# ivo_B_v1_1.net
KiCad netlist of a schematic drawn in EAGLE
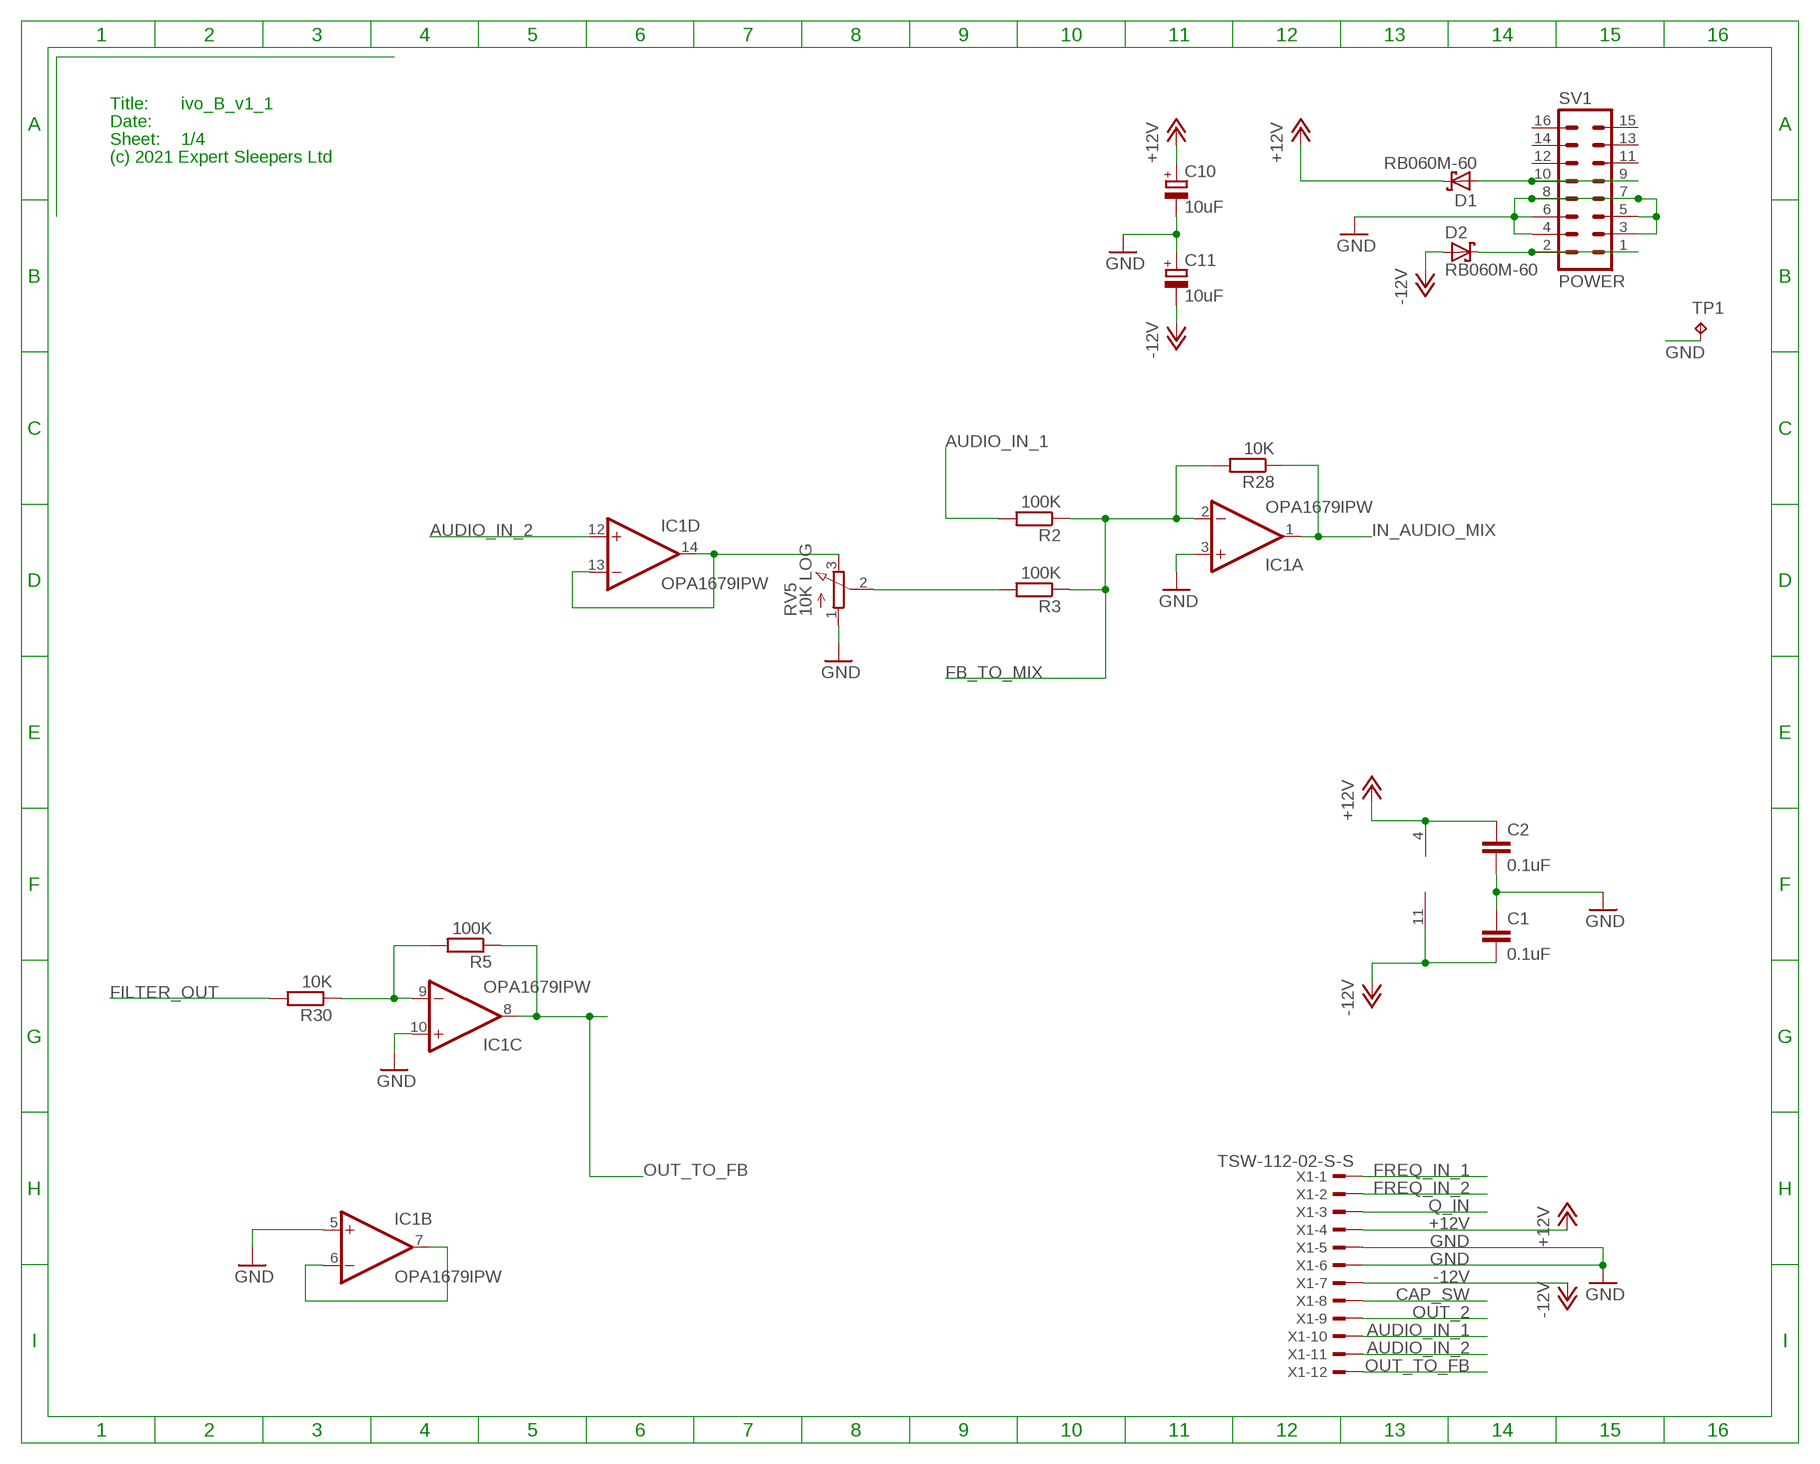
[diagram p0: schematic, sheet 1]
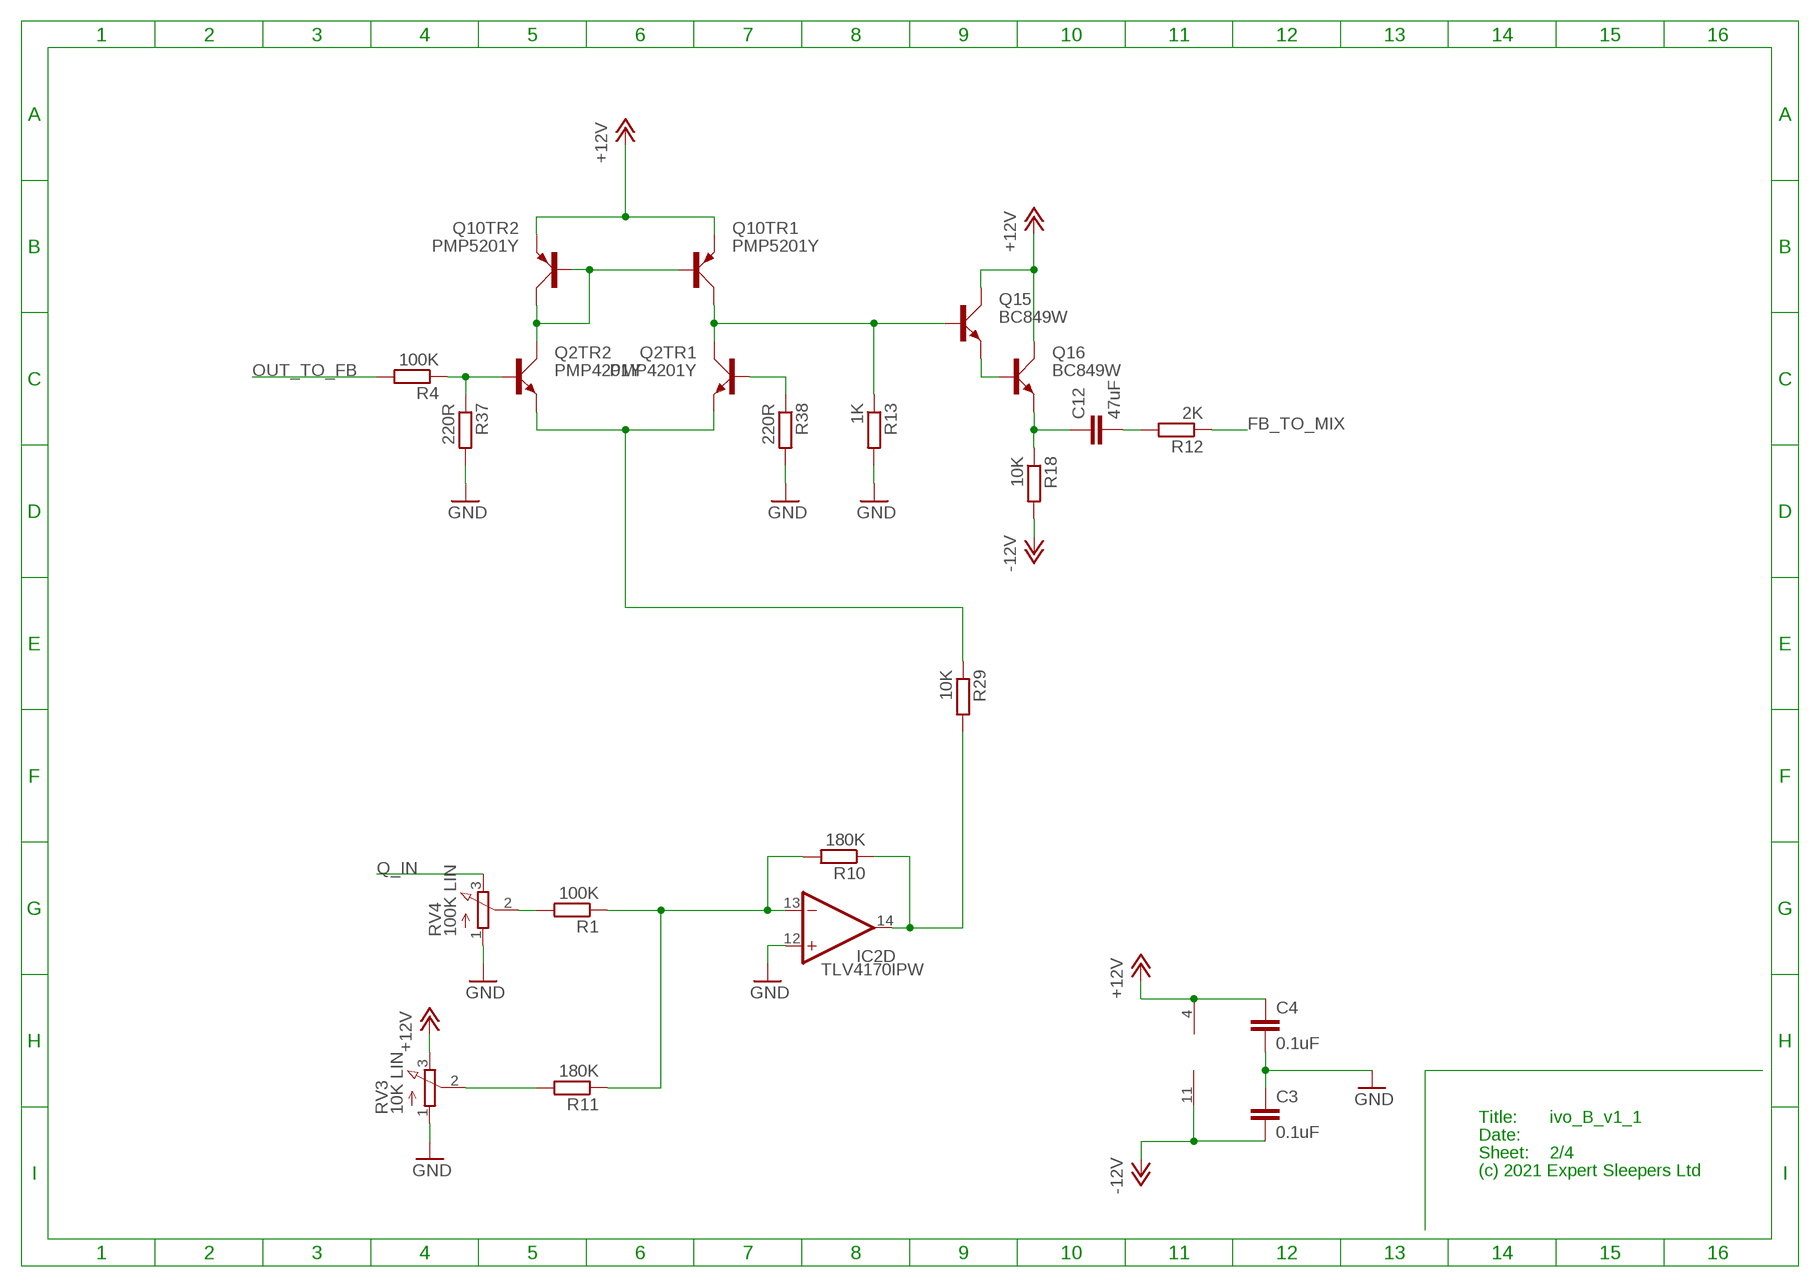
[diagram p1: schematic, sheet 2]
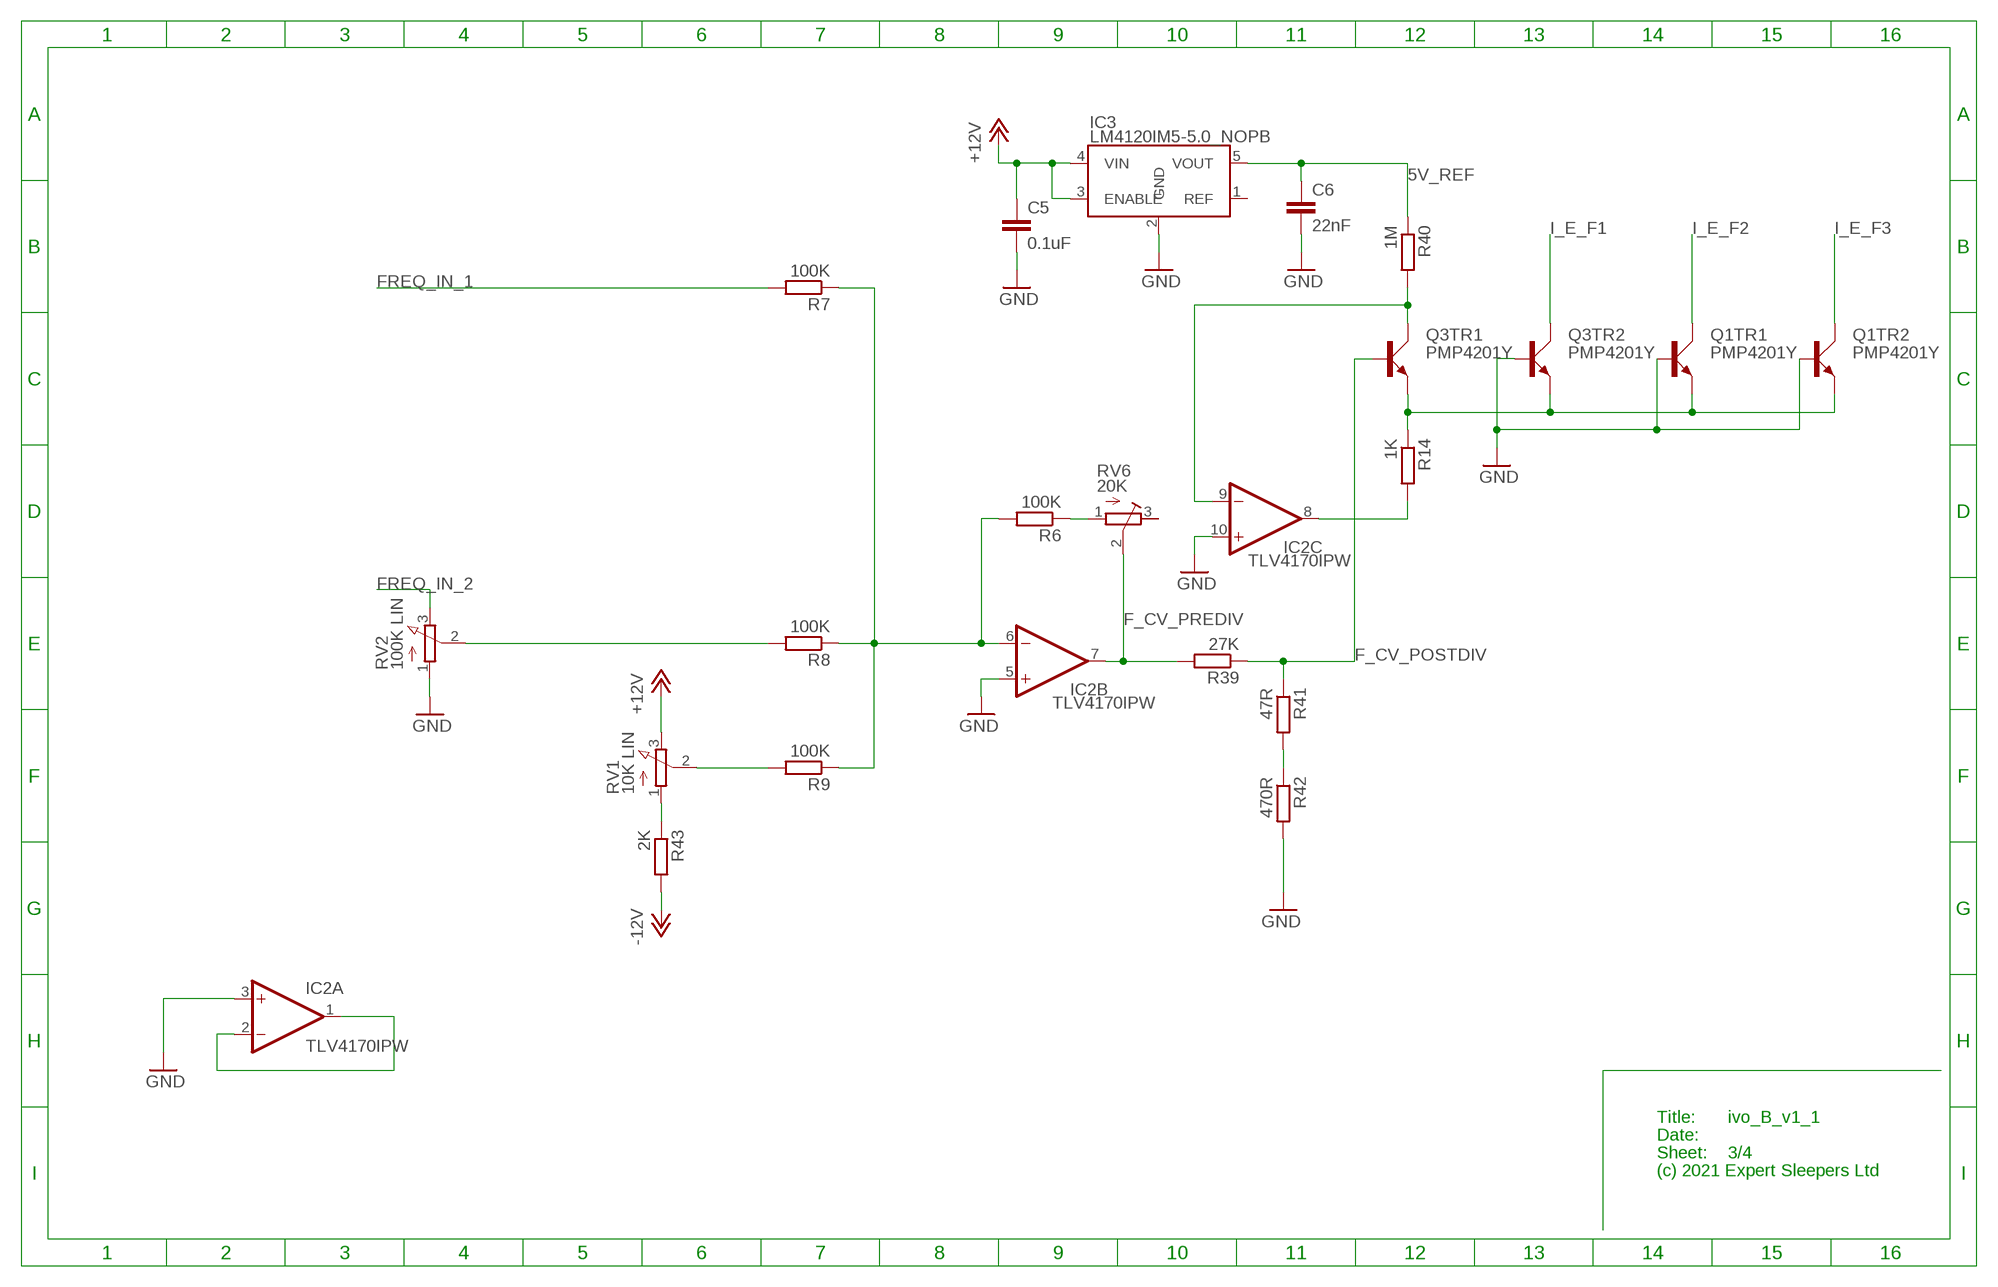
[diagram p2: schematic, sheet 3]
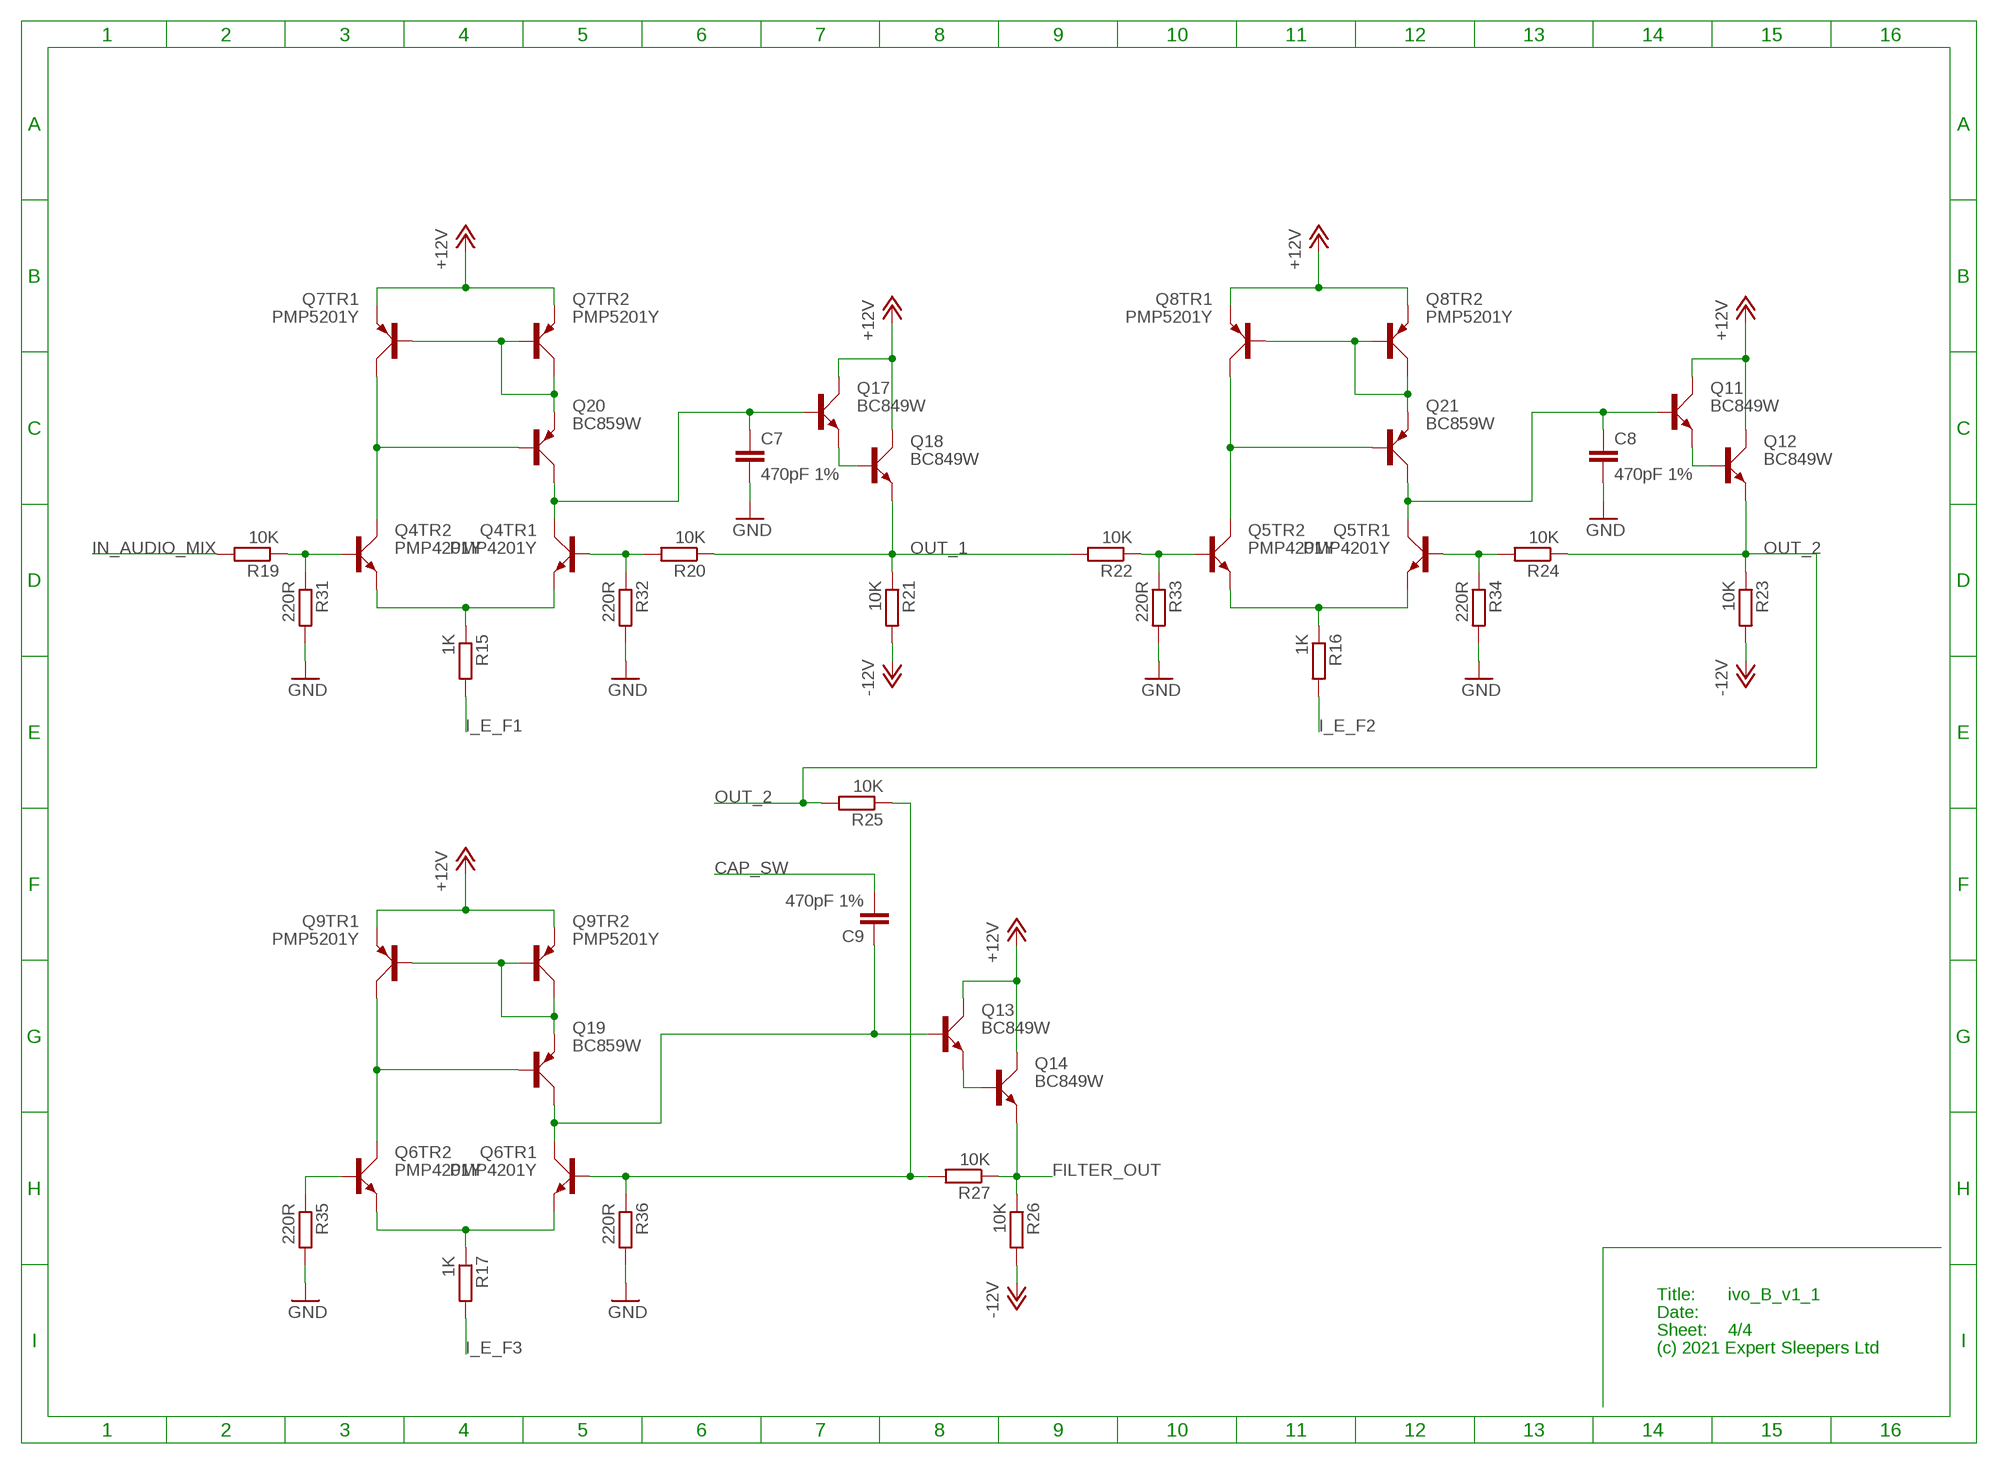
[diagram p3: schematic, sheet 4]

(export (version "E")
  (design (tool "Eeschema 10.0.6"))
  (components
    (comp (ref "C5")
      (value "0.1uF")
      (footprint "eagle-import:C0402")
      (libsource (lib "eagle-import") (part "C-EUC0402"))
    )
    (comp (ref "C6")
      (value "22nF")
      (footprint "eagle-import:C0402")
      (libsource (lib "eagle-import") (part "C-EUC0402"))
    )
    (comp (ref "IC2")
      (value "TLV4170IPW")
      (footprint "eagle-import:PW_R-PDSO-G14")
      (libsource (lib "eagle-import") (part "TL074PW"))
    )
    (comp (ref "IC3")
      (value "LM4120IM5-5.0_NOPB")
      (footprint "eagle-import:SOT95P280X145-5N")
      (fields
        (field (name "ARROW_PART_NUMBER") "LM4120IM5-5.0/NOPB")
        (field (name "MOUSER_PART_NUMBER") "926-LM4120IM550NOPB")
      )
      (libsource (lib "eagle-import") (part "LM4120IM5-5.0_NOPB"))
    )
    (comp (ref "Q1")
      (value "PMP4201Y")
      (footprint "eagle-import:SOT65P210X110-6N")
      (fields
        (field (name "ARROW_PART_NUMBER") "PMP4201Y,135")
        (field (name "MOUSER_PART_NUMBER") "771-PMP4201Y135")
      )
      (libsource (lib "eagle-import") (part "PMP4201Y"))
    )
    (comp (ref "Q3")
      (value "PMP4201Y")
      (footprint "eagle-import:SOT65P210X110-6N")
      (fields
        (field (name "ARROW_PART_NUMBER") "PMP4201Y,135")
        (field (name "MOUSER_PART_NUMBER") "771-PMP4201Y135")
      )
      (libsource (lib "eagle-import") (part "PMP4201Y"))
    )
    (comp (ref "R6")
      (value "100K")
      (footprint "eagle-import:R0603")
      (libsource (lib "eagle-import") (part "R-EU_R0603"))
    )
    (comp (ref "R7")
      (value "100K")
      (footprint "eagle-import:R0603")
      (libsource (lib "eagle-import") (part "R-EU_R0603"))
    )
    (comp (ref "R8")
      (value "100K")
      (footprint "eagle-import:R0603")
      (libsource (lib "eagle-import") (part "R-EU_R0603"))
    )
    (comp (ref "R9")
      (value "100K")
      (footprint "eagle-import:R0603")
      (libsource (lib "eagle-import") (part "R-EU_R0603"))
    )
    (comp (ref "R14")
      (value "1K")
      (footprint "eagle-import:R0603")
      (libsource (lib "eagle-import") (part "R-EU_R0603"))
    )
    (comp (ref "R39")
      (value "27K")
      (footprint "eagle-import:R0603")
      (libsource (lib "eagle-import") (part "R-EU_R0603"))
    )
    (comp (ref "R40")
      (value "1M")
      (footprint "eagle-import:R0603")
      (libsource (lib "eagle-import") (part "R-EU_R0603"))
    )
    (comp (ref "R41")
      (value "47R")
      (footprint "eagle-import:R0603")
      (libsource (lib "eagle-import") (part "R-EU_R0603"))
    )
    (comp (ref "R42")
      (value "470R")
      (footprint "eagle-import:R1206")
      (libsource (lib "eagle-import") (part "R-EU_R1206"))
    )
    (comp (ref "R43")
      (value "2K")
      (footprint "eagle-import:R0603")
      (libsource (lib "eagle-import") (part "R-EU_R0603"))
    )
    (comp (ref "RV1")
      (value "10K LIN")
      (footprint "eagle-import:RD1610NOA0X")
      (libsource (lib "eagle-import") (part "RD1610NOA0X"))
    )
    (comp (ref "RV2")
      (value "100K LIN")
      (footprint "eagle-import:RD1610NOA0X")
      (libsource (lib "eagle-import") (part "RD1610NOA0X"))
    )
    (comp (ref "RV6")
      (value "20K")
      (footprint "eagle-import:TC33X")
      (libsource (lib "eagle-import") (part "TC33X"))
    )
    (comp (ref "C1")
      (value "0.1uF")
      (footprint "eagle-import:C0402")
      (libsource (lib "eagle-import") (part "C-EUC0402"))
    )
    (comp (ref "C2")
      (value "0.1uF")
      (footprint "eagle-import:C0402")
      (libsource (lib "eagle-import") (part "C-EUC0402"))
    )
    (comp (ref "C10")
      (value "10uF")
      (footprint "eagle-import:UD-4X5,8_NICHICON")
      (libsource (lib "eagle-import") (part "CPOL-EUUD-4X5,8"))
    )
    (comp (ref "C11")
      (value "10uF")
      (footprint "eagle-import:UD-4X5,8_NICHICON")
      (libsource (lib "eagle-import") (part "CPOL-EUUD-4X5,8"))
    )
    (comp (ref "D1")
      (value "RB060M-60")
      (footprint "eagle-import:SOD123FL")
      (libsource (lib "eagle-import") (part "RB060M-60"))
    )
    (comp (ref "D2")
      (value "RB060M-60")
      (footprint "eagle-import:SOD123FL")
      (libsource (lib "eagle-import") (part "RB060M-60"))
    )
    (comp (ref "IC1")
      (value "OPA1679IPW")
      (footprint "eagle-import:PW_R-PDSO-G14")
      (libsource (lib "eagle-import") (part "TL074PW"))
    )
    (comp (ref "R2")
      (value "100K")
      (footprint "eagle-import:R0603")
      (libsource (lib "eagle-import") (part "R-EU_R0603"))
    )
    (comp (ref "R3")
      (value "100K")
      (footprint "eagle-import:R0603")
      (libsource (lib "eagle-import") (part "R-EU_R0603"))
    )
    (comp (ref "R5")
      (value "100K")
      (footprint "eagle-import:R0603")
      (libsource (lib "eagle-import") (part "R-EU_R0603"))
    )
    (comp (ref "R28")
      (value "10K")
      (footprint "eagle-import:R0603")
      (libsource (lib "eagle-import") (part "R-EU_R0603"))
    )
    (comp (ref "R30")
      (value "10K")
      (footprint "eagle-import:R0603")
      (libsource (lib "eagle-import") (part "R-EU_R0603"))
    )
    (comp (ref "RV5")
      (value "10K LOG")
      (footprint "eagle-import:RD1610NOA0X")
      (libsource (lib "eagle-import") (part "RD1610NOA0X"))
    )
    (comp (ref "SV1")
      (value "POWER")
      (footprint "eagle-import:ML16")
      (libsource (lib "eagle-import") (part "ML16"))
    )
    (comp (ref "TP1")
      (value "RA2")
      (footprint "eagle-import:P1-13")
      (libsource (lib "eagle-import") (part "TPPAD1-13"))
    )
    (comp (ref "X1")
      (value "TSW-112-02-S-S")
      (footprint "eagle-import:TSW-112-02-S-S")
      (libsource (lib "eagle-import") (part "TSW-112-02-S-S"))
    )
    (comp (ref "C3")
      (value "0.1uF")
      (footprint "eagle-import:C0402")
      (libsource (lib "eagle-import") (part "C-EUC0402"))
    )
    (comp (ref "C4")
      (value "0.1uF")
      (footprint "eagle-import:C0402")
      (libsource (lib "eagle-import") (part "C-EUC0402"))
    )
    (comp (ref "C12")
      (value "47uF")
      (footprint "eagle-import:C1206")
      (libsource (lib "eagle-import") (part "C-EUC1206"))
    )
    (comp (ref "Q2")
      (value "PMP4201Y")
      (footprint "eagle-import:SOT65P210X110-6N")
      (fields
        (field (name "ARROW_PART_NUMBER") "PMP4201Y,135")
        (field (name "MOUSER_PART_NUMBER") "771-PMP4201Y135")
      )
      (libsource (lib "eagle-import") (part "PMP4201Y"))
    )
    (comp (ref "Q10")
      (value "PMP5201Y")
      (footprint "eagle-import:SOT65P210X110-6N")
      (fields
        (field (name "ARROW_PART_NUMBER") "PMP5201Y,135")
        (field (name "MOUSER_PART_NUMBER") "771-PMP5201Y135")
      )
      (libsource (lib "eagle-import") (part "PMP5201Y"))
    )
    (comp (ref "Q15")
      (value "BC849W")
      (footprint "eagle-import:SOT323")
      (libsource (lib "eagle-import") (part "BC849W"))
    )
    (comp (ref "Q16")
      (value "BC849W")
      (footprint "eagle-import:SOT323")
      (libsource (lib "eagle-import") (part "BC849W"))
    )
    (comp (ref "R1")
      (value "100K")
      (footprint "eagle-import:R0603")
      (libsource (lib "eagle-import") (part "R-EU_R0603"))
    )
    (comp (ref "R4")
      (value "100K")
      (footprint "eagle-import:R0603")
      (libsource (lib "eagle-import") (part "R-EU_R0603"))
    )
    (comp (ref "R10")
      (value "180K")
      (footprint "eagle-import:R0603")
      (libsource (lib "eagle-import") (part "R-EU_R0603"))
    )
    (comp (ref "R11")
      (value "180K")
      (footprint "eagle-import:R0603")
      (libsource (lib "eagle-import") (part "R-EU_R0603"))
    )
    (comp (ref "R12")
      (value "2K")
      (footprint "eagle-import:R0603")
      (libsource (lib "eagle-import") (part "R-EU_R0603"))
    )
    (comp (ref "R13")
      (value "1K")
      (footprint "eagle-import:R0603")
      (libsource (lib "eagle-import") (part "R-EU_R0603"))
    )
    (comp (ref "R18")
      (value "10K")
      (footprint "eagle-import:R0603")
      (libsource (lib "eagle-import") (part "R-EU_R0603"))
    )
    (comp (ref "R29")
      (value "10K")
      (footprint "eagle-import:R0603")
      (libsource (lib "eagle-import") (part "R-EU_R0603"))
    )
    (comp (ref "R37")
      (value "220R")
      (footprint "eagle-import:R0603")
      (libsource (lib "eagle-import") (part "R-EU_R0603"))
    )
    (comp (ref "R38")
      (value "220R")
      (footprint "eagle-import:R0603")
      (libsource (lib "eagle-import") (part "R-EU_R0603"))
    )
    (comp (ref "RV3")
      (value "10K LIN")
      (footprint "eagle-import:RD1610NOA0X")
      (libsource (lib "eagle-import") (part "RD1610NOA0X"))
    )
    (comp (ref "RV4")
      (value "100K LIN")
      (footprint "eagle-import:RD1610NOA0X")
      (libsource (lib "eagle-import") (part "RD1610NOA0X"))
    )
    (comp (ref "C7")
      (value "470pF 1%")
      (footprint "eagle-import:C0603")
      (libsource (lib "eagle-import") (part "C-EUC0603"))
    )
    (comp (ref "C8")
      (value "470pF 1%")
      (footprint "eagle-import:C0603")
      (libsource (lib "eagle-import") (part "C-EUC0603"))
    )
    (comp (ref "C9")
      (value "470pF 1%")
      (footprint "eagle-import:C0603")
      (libsource (lib "eagle-import") (part "C-EUC0603"))
    )
    (comp (ref "Q4")
      (value "PMP4201Y")
      (footprint "eagle-import:SOT65P210X110-6N")
      (fields
        (field (name "ARROW_PART_NUMBER") "PMP4201Y,135")
        (field (name "MOUSER_PART_NUMBER") "771-PMP4201Y135")
      )
      (libsource (lib "eagle-import") (part "PMP4201Y"))
    )
    (comp (ref "Q5")
      (value "PMP4201Y")
      (footprint "eagle-import:SOT65P210X110-6N")
      (fields
        (field (name "ARROW_PART_NUMBER") "PMP4201Y,135")
        (field (name "MOUSER_PART_NUMBER") "771-PMP4201Y135")
      )
      (libsource (lib "eagle-import") (part "PMP4201Y"))
    )
    (comp (ref "Q6")
      (value "PMP4201Y")
      (footprint "eagle-import:SOT65P210X110-6N")
      (fields
        (field (name "ARROW_PART_NUMBER") "PMP4201Y,135")
        (field (name "MOUSER_PART_NUMBER") "771-PMP4201Y135")
      )
      (libsource (lib "eagle-import") (part "PMP4201Y"))
    )
    (comp (ref "Q7")
      (value "PMP5201Y")
      (footprint "eagle-import:SOT65P210X110-6N")
      (fields
        (field (name "ARROW_PART_NUMBER") "PMP5201Y,135")
        (field (name "MOUSER_PART_NUMBER") "771-PMP5201Y135")
      )
      (libsource (lib "eagle-import") (part "PMP5201Y"))
    )
    (comp (ref "Q8")
      (value "PMP5201Y")
      (footprint "eagle-import:SOT65P210X110-6N")
      (fields
        (field (name "ARROW_PART_NUMBER") "PMP5201Y,135")
        (field (name "MOUSER_PART_NUMBER") "771-PMP5201Y135")
      )
      (libsource (lib "eagle-import") (part "PMP5201Y"))
    )
    (comp (ref "Q9")
      (value "PMP5201Y")
      (footprint "eagle-import:SOT65P210X110-6N")
      (fields
        (field (name "ARROW_PART_NUMBER") "PMP5201Y,135")
        (field (name "MOUSER_PART_NUMBER") "771-PMP5201Y135")
      )
      (libsource (lib "eagle-import") (part "PMP5201Y"))
    )
    (comp (ref "Q11")
      (value "BC849W")
      (footprint "eagle-import:SOT323")
      (libsource (lib "eagle-import") (part "BC849W"))
    )
    (comp (ref "Q12")
      (value "BC849W")
      (footprint "eagle-import:SOT323")
      (libsource (lib "eagle-import") (part "BC849W"))
    )
    (comp (ref "Q13")
      (value "BC849W")
      (footprint "eagle-import:SOT323")
      (libsource (lib "eagle-import") (part "BC849W"))
    )
    (comp (ref "Q14")
      (value "BC849W")
      (footprint "eagle-import:SOT323")
      (libsource (lib "eagle-import") (part "BC849W"))
    )
    (comp (ref "Q17")
      (value "BC849W")
      (footprint "eagle-import:SOT323")
      (libsource (lib "eagle-import") (part "BC849W"))
    )
    (comp (ref "Q18")
      (value "BC849W")
      (footprint "eagle-import:SOT323")
      (libsource (lib "eagle-import") (part "BC849W"))
    )
    (comp (ref "Q19")
      (value "BC859W")
      (footprint "eagle-import:SOT323")
      (libsource (lib "eagle-import") (part "BC859W"))
    )
    (comp (ref "Q20")
      (value "BC859W")
      (footprint "eagle-import:SOT323")
      (libsource (lib "eagle-import") (part "BC859W"))
    )
    (comp (ref "Q21")
      (value "BC859W")
      (footprint "eagle-import:SOT323")
      (libsource (lib "eagle-import") (part "BC859W"))
    )
    (comp (ref "R15")
      (value "1K")
      (footprint "eagle-import:R0603")
      (libsource (lib "eagle-import") (part "R-EU_R0603"))
    )
    (comp (ref "R16")
      (value "1K")
      (footprint "eagle-import:R0603")
      (libsource (lib "eagle-import") (part "R-EU_R0603"))
    )
    (comp (ref "R17")
      (value "1K")
      (footprint "eagle-import:R0603")
      (libsource (lib "eagle-import") (part "R-EU_R0603"))
    )
    (comp (ref "R19")
      (value "10K")
      (footprint "eagle-import:R0603")
      (libsource (lib "eagle-import") (part "R-EU_R0603"))
    )
    (comp (ref "R20")
      (value "10K")
      (footprint "eagle-import:R0603")
      (libsource (lib "eagle-import") (part "R-EU_R0603"))
    )
    (comp (ref "R21")
      (value "10K")
      (footprint "eagle-import:R0603")
      (libsource (lib "eagle-import") (part "R-EU_R0603"))
    )
    (comp (ref "R22")
      (value "10K")
      (footprint "eagle-import:R0603")
      (libsource (lib "eagle-import") (part "R-EU_R0603"))
    )
    (comp (ref "R23")
      (value "10K")
      (footprint "eagle-import:R0603")
      (libsource (lib "eagle-import") (part "R-EU_R0603"))
    )
    (comp (ref "R24")
      (value "10K")
      (footprint "eagle-import:R0603")
      (libsource (lib "eagle-import") (part "R-EU_R0603"))
    )
    (comp (ref "R25")
      (value "10K")
      (footprint "eagle-import:R0603")
      (libsource (lib "eagle-import") (part "R-EU_R0603"))
    )
    (comp (ref "R26")
      (value "10K")
      (footprint "eagle-import:R0603")
      (libsource (lib "eagle-import") (part "R-EU_R0603"))
    )
    (comp (ref "R27")
      (value "10K")
      (footprint "eagle-import:R0603")
      (libsource (lib "eagle-import") (part "R-EU_R0603"))
    )
    (comp (ref "R31")
      (value "220R")
      (footprint "eagle-import:R0603")
      (libsource (lib "eagle-import") (part "R-EU_R0603"))
    )
    (comp (ref "R32")
      (value "220R")
      (footprint "eagle-import:R0603")
      (libsource (lib "eagle-import") (part "R-EU_R0603"))
    )
    (comp (ref "R33")
      (value "220R")
      (footprint "eagle-import:R0603")
      (libsource (lib "eagle-import") (part "R-EU_R0603"))
    )
    (comp (ref "R34")
      (value "220R")
      (footprint "eagle-import:R0603")
      (libsource (lib "eagle-import") (part "R-EU_R0603"))
    )
    (comp (ref "R35")
      (value "220R")
      (footprint "eagle-import:R0603")
      (libsource (lib "eagle-import") (part "R-EU_R0603"))
    )
    (comp (ref "R36")
      (value "220R")
      (footprint "eagle-import:R0603")
      (libsource (lib "eagle-import") (part "R-EU_R0603"))
    )
  )
  (nets
    (net (code "1") (name "+12V") (class "Default")
      (node (ref "C10") (pin "+") (pinfunction "+_+") (pintype "passive"))
      (node (ref "C2") (pin "1") (pinfunction "1_1") (pintype "passive"))
      (node (ref "C4") (pin "1") (pinfunction "1_1") (pintype "passive"))
      (node (ref "C5") (pin "1") (pinfunction "1_1") (pintype "passive"))
      (node (ref "D1") (pin "C") (pinfunction "C_C") (pintype "passive"))
      (node (ref "IC1") (pin "4") (pinfunction "V+_4") (pintype "power_in"))
      (node (ref "IC2") (pin "4") (pinfunction "V+_4") (pintype "power_in"))
      (node (ref "IC3") (pin "3") (pinfunction "ENABLE_3") (pintype "input"))
      (node (ref "IC3") (pin "4") (pinfunction "VIN_4") (pintype "power_in"))
      (node (ref "Q10") (pin "4") (pinfunction "E_4") (pintype "passive"))
      (node (ref "Q10") (pin "5") (pinfunction "E_5") (pintype "passive"))
      (node (ref "Q11") (pin "3") (pinfunction "C_3") (pintype "passive"))
      (node (ref "Q12") (pin "3") (pinfunction "C_3") (pintype "passive"))
      (node (ref "Q13") (pin "3") (pinfunction "C_3") (pintype "passive"))
      (node (ref "Q14") (pin "3") (pinfunction "C_3") (pintype "passive"))
      (node (ref "Q15") (pin "3") (pinfunction "C_3") (pintype "passive"))
      (node (ref "Q16") (pin "3") (pinfunction "C_3") (pintype "passive"))
      (node (ref "Q17") (pin "3") (pinfunction "C_3") (pintype "passive"))
      (node (ref "Q18") (pin "3") (pinfunction "C_3") (pintype "passive"))
      (node (ref "Q7") (pin "4") (pinfunction "E_4") (pintype "passive"))
      (node (ref "Q7") (pin "5") (pinfunction "E_5") (pintype "passive"))
      (node (ref "Q8") (pin "4") (pinfunction "E_4") (pintype "passive"))
      (node (ref "Q8") (pin "5") (pinfunction "E_5") (pintype "passive"))
      (node (ref "Q9") (pin "4") (pinfunction "E_4") (pintype "passive"))
      (node (ref "Q9") (pin "5") (pinfunction "E_5") (pintype "passive"))
      (node (ref "RV1") (pin "3") (pinfunction "E_3") (pintype "passive"))
      (node (ref "RV3") (pin "3") (pinfunction "E_3") (pintype "passive"))
      (node (ref "X1") (pin "4") (pinfunction "1_4") (pintype "passive"))
    )
    (net (code "2") (name "-12V") (class "Default")
      (node (ref "C1") (pin "2") (pinfunction "2_2") (pintype "passive"))
      (node (ref "C11") (pin "-") (pinfunction "-_-") (pintype "passive"))
      (node (ref "C3") (pin "2") (pinfunction "2_2") (pintype "passive"))
      (node (ref "D2") (pin "A") (pinfunction "A_A") (pintype "passive"))
      (node (ref "IC1") (pin "11") (pinfunction "V-_11") (pintype "power_in"))
      (node (ref "IC2") (pin "11") (pinfunction "V-_11") (pintype "power_in"))
      (node (ref "R18") (pin "2") (pinfunction "2_2") (pintype "passive"))
      (node (ref "R21") (pin "2") (pinfunction "2_2") (pintype "passive"))
      (node (ref "R23") (pin "2") (pinfunction "2_2") (pintype "passive"))
      (node (ref "R26") (pin "2") (pinfunction "2_2") (pintype "passive"))
      (node (ref "R43") (pin "2") (pinfunction "2_2") (pintype "passive"))
      (node (ref "X1") (pin "7") (pinfunction "1_7") (pintype "passive"))
    )
    (net (code "3") (name "5V_REF") (class "Default")
      (node (ref "C6") (pin "1") (pinfunction "1_1") (pintype "passive"))
      (node (ref "IC3") (pin "5") (pinfunction "VOUT_5") (pintype "output"))
      (node (ref "R40") (pin "1") (pinfunction "1_1") (pintype "passive"))
    )
    (net (code "4") (name "AUDIO_IN_1") (class "Default")
      (node (ref "R2") (pin "2") (pinfunction "2_2") (pintype "passive"))
      (node (ref "X1") (pin "10") (pinfunction "1_10") (pintype "passive"))
    )
    (net (code "5") (name "AUDIO_IN_2") (class "Default")
      (node (ref "IC1") (pin "12") (pinfunction "+IN_12") (pintype "input"))
      (node (ref "X1") (pin "11") (pinfunction "1_11") (pintype "passive"))
    )
    (net (code "6") (name "CAP_SW") (class "Default")
      (node (ref "C9") (pin "2") (pinfunction "2_2") (pintype "passive"))
      (node (ref "X1") (pin "8") (pinfunction "1_8") (pintype "passive"))
    )
    (net (code "7") (name "FB_TO_MIX") (class "Default")
      (node (ref "IC1") (pin "2") (pinfunction "-IN_2") (pintype "input"))
      (node (ref "R12") (pin "1") (pinfunction "1_1") (pintype "passive"))
      (node (ref "R2") (pin "1") (pinfunction "1_1") (pintype "passive"))
      (node (ref "R28") (pin "2") (pinfunction "2_2") (pintype "passive"))
      (node (ref "R3") (pin "1") (pinfunction "1_1") (pintype "passive"))
    )
    (net (code "8") (name "FILTER_OUT") (class "Default")
      (node (ref "Q14") (pin "2") (pinfunction "E_2") (pintype "passive"))
      (node (ref "R26") (pin "1") (pinfunction "1_1") (pintype "passive"))
      (node (ref "R27") (pin "1") (pinfunction "1_1") (pintype "passive"))
      (node (ref "R30") (pin "2") (pinfunction "2_2") (pintype "passive"))
    )
    (net (code "9") (name "FREQ_IN_1") (class "Default")
      (node (ref "R7") (pin "2") (pinfunction "2_2") (pintype "passive"))
      (node (ref "X1") (pin "1") (pinfunction "1_1") (pintype "passive"))
    )
    (net (code "10") (name "FREQ_IN_2") (class "Default")
      (node (ref "RV2") (pin "3") (pinfunction "E_3") (pintype "passive"))
      (node (ref "X1") (pin "2") (pinfunction "1_2") (pintype "passive"))
    )
    (net (code "11") (name "F_CV_POSTDIV") (class "Default")
      (node (ref "Q3") (pin "1") (pinfunction "B_1") (pintype "passive"))
      (node (ref "R39") (pin "1") (pinfunction "1_1") (pintype "passive"))
      (node (ref "R41") (pin "1") (pinfunction "1_1") (pintype "passive"))
    )
    (net (code "12") (name "F_CV_PREDIV") (class "Default")
      (node (ref "IC2") (pin "7") (pinfunction "OUT_7") (pintype "output"))
      (node (ref "R39") (pin "2") (pinfunction "2_2") (pintype "passive"))
      (node (ref "RV6") (pin "2") (pinfunction "S_2") (pintype "passive"))
    )
    (net (code "13") (name "GND") (class "Default")
      (node (ref "C1") (pin "1") (pinfunction "1_1") (pintype "passive"))
      (node (ref "C10") (pin "-") (pinfunction "-_-") (pintype "passive"))
      (node (ref "C11") (pin "+") (pinfunction "+_+") (pintype "passive"))
      (node (ref "C2") (pin "2") (pinfunction "2_2") (pintype "passive"))
      (node (ref "C3") (pin "1") (pinfunction "1_1") (pintype "passive"))
      (node (ref "C4") (pin "2") (pinfunction "2_2") (pintype "passive"))
      (node (ref "C5") (pin "2") (pinfunction "2_2") (pintype "passive"))
      (node (ref "C6") (pin "2") (pinfunction "2_2") (pintype "passive"))
      (node (ref "C7") (pin "2") (pinfunction "2_2") (pintype "passive"))
      (node (ref "C8") (pin "2") (pinfunction "2_2") (pintype "passive"))
      (node (ref "IC1") (pin "10") (pinfunction "+IN_10") (pintype "input"))
      (node (ref "IC1") (pin "3") (pinfunction "+IN_3") (pintype "input"))
      (node (ref "IC1") (pin "5") (pinfunction "+IN_5") (pintype "input"))
      (node (ref "IC2") (pin "10") (pinfunction "+IN_10") (pintype "input"))
      (node (ref "IC2") (pin "12") (pinfunction "+IN_12") (pintype "input"))
      (node (ref "IC2") (pin "3") (pinfunction "+IN_3") (pintype "input"))
      (node (ref "IC2") (pin "5") (pinfunction "+IN_5") (pintype "input"))
      (node (ref "IC3") (pin "2") (pinfunction "GND_2") (pintype "power_in"))
      (node (ref "Q1") (pin "1") (pinfunction "B_1") (pintype "passive"))
      (node (ref "Q1") (pin "2") (pinfunction "B_2") (pintype "passive"))
      (node (ref "Q3") (pin "2") (pinfunction "B_2") (pintype "passive"))
      (node (ref "R13") (pin "2") (pinfunction "2_2") (pintype "passive"))
      (node (ref "R31") (pin "2") (pinfunction "2_2") (pintype "passive"))
      (node (ref "R32") (pin "2") (pinfunction "2_2") (pintype "passive"))
      (node (ref "R33") (pin "2") (pinfunction "2_2") (pintype "passive"))
      (node (ref "R34") (pin "2") (pinfunction "2_2") (pintype "passive"))
      (node (ref "R35") (pin "2") (pinfunction "2_2") (pintype "passive"))
      (node (ref "R36") (pin "2") (pinfunction "2_2") (pintype "passive"))
      (node (ref "R37") (pin "2") (pinfunction "2_2") (pintype "passive"))
      (node (ref "R38") (pin "2") (pinfunction "2_2") (pintype "passive"))
      (node (ref "R42") (pin "2") (pinfunction "2_2") (pintype "passive"))
      (node (ref "RV2") (pin "1") (pinfunction "A_1") (pintype "passive"))
      (node (ref "RV3") (pin "1") (pinfunction "A_1") (pintype "passive"))
      (node (ref "RV4") (pin "1") (pinfunction "A_1") (pintype "passive"))
      (node (ref "RV5") (pin "1") (pinfunction "A_1") (pintype "passive"))
      (node (ref "SV1") (pin "3") (pinfunction "3_3") (pintype "passive"))
      (node (ref "SV1") (pin "4") (pinfunction "4_4") (pintype "passive"))
      (node (ref "SV1") (pin "5") (pinfunction "5_5") (pintype "passive"))
      (node (ref "SV1") (pin "6") (pinfunction "6_6") (pintype "passive"))
      (node (ref "SV1") (pin "7") (pinfunction "7_7") (pintype "passive"))
      (node (ref "SV1") (pin "8") (pinfunction "8_8") (pintype "passive"))
      (node (ref "TP1") (pin "TP") (pinfunction "TP_TP") (pintype "input"))
      (node (ref "X1") (pin "5") (pinfunction "1_5") (pintype "passive"))
      (node (ref "X1") (pin "6") (pinfunction "1_6") (pintype "passive"))
    )
    (net (code "14") (name "IN_AUDIO_MIX") (class "Default")
      (node (ref "IC1") (pin "1") (pinfunction "OUT_1") (pintype "output"))
      (node (ref "R19") (pin "2") (pinfunction "2_2") (pintype "passive"))
      (node (ref "R28") (pin "1") (pinfunction "1_1") (pintype "passive"))
    )
    (net (code "15") (name "I_E_F1") (class "Default")
      (node (ref "Q3") (pin "3") (pinfunction "C_3") (pintype "passive"))
      (node (ref "R15") (pin "2") (pinfunction "2_2") (pintype "passive"))
    )
    (net (code "16") (name "I_E_F2") (class "Default")
      (node (ref "Q1") (pin "6") (pinfunction "C_6") (pintype "passive"))
      (node (ref "R16") (pin "2") (pinfunction "2_2") (pintype "passive"))
    )
    (net (code "17") (name "I_E_F3") (class "Default")
      (node (ref "Q1") (pin "3") (pinfunction "C_3") (pintype "passive"))
      (node (ref "R17") (pin "2") (pinfunction "2_2") (pintype "passive"))
    )
    (net (code "18") (name "Net-(C12-Pad2)") (class "Default")
      (node (ref "C12") (pin "2") (pinfunction "2_2") (pintype "passive"))
      (node (ref "R12") (pin "2") (pinfunction "2_2") (pintype "passive"))
    )
    (net (code "19") (name "Net-(D1-PadA)") (class "Default")
      (node (ref "D1") (pin "A") (pinfunction "A_A") (pintype "passive"))
      (node (ref "SV1") (pin "10") (pinfunction "10_10") (pintype "passive"))
      (node (ref "SV1") (pin "9") (pinfunction "9_9") (pintype "passive"))
    )
    (net (code "20") (name "Net-(D2-PadC)") (class "Default")
      (node (ref "D2") (pin "C") (pinfunction "C_C") (pintype "passive"))
      (node (ref "SV1") (pin "1") (pinfunction "1_1") (pintype "passive"))
      (node (ref "SV1") (pin "2") (pinfunction "2_2") (pintype "passive"))
    )
    (net (code "21") (name "Net-(IC1B--IN)") (class "Default")
      (node (ref "IC1") (pin "6") (pinfunction "-IN_6") (pintype "input"))
      (node (ref "IC1") (pin "7") (pinfunction "OUT_7") (pintype "output"))
    )
    (net (code "22") (name "Net-(IC1C--IN)") (class "Default")
      (node (ref "IC1") (pin "9") (pinfunction "-IN_9") (pintype "input"))
      (node (ref "R30") (pin "1") (pinfunction "1_1") (pintype "passive"))
      (node (ref "R5") (pin "2") (pinfunction "2_2") (pintype "passive"))
    )
    (net (code "23") (name "Net-(IC1D--IN)") (class "Default")
      (node (ref "IC1") (pin "13") (pinfunction "-IN_13") (pintype "input"))
      (node (ref "IC1") (pin "14") (pinfunction "OUT_14") (pintype "output"))
      (node (ref "RV5") (pin "3") (pinfunction "E_3") (pintype "passive"))
    )
    (net (code "24") (name "Net-(IC2A--IN)") (class "Default")
      (node (ref "IC2") (pin "1") (pinfunction "OUT_1") (pintype "output"))
      (node (ref "IC2") (pin "2") (pinfunction "-IN_2") (pintype "input"))
    )
    (net (code "25") (name "Net-(IC2B--IN)") (class "Default")
      (node (ref "IC2") (pin "6") (pinfunction "-IN_6") (pintype "input"))
      (node (ref "R6") (pin "2") (pinfunction "2_2") (pintype "passive"))
      (node (ref "R7") (pin "1") (pinfunction "1_1") (pintype "passive"))
      (node (ref "R8") (pin "1") (pinfunction "1_1") (pintype "passive"))
      (node (ref "R9") (pin "1") (pinfunction "1_1") (pintype "passive"))
    )
    (net (code "26") (name "Net-(IC2C--IN)") (class "Default")
      (node (ref "IC2") (pin "9") (pinfunction "-IN_9") (pintype "input"))
      (node (ref "Q3") (pin "6") (pinfunction "C_6") (pintype "passive"))
      (node (ref "R40") (pin "2") (pinfunction "2_2") (pintype "passive"))
    )
    (net (code "27") (name "Net-(IC2C-OUT)") (class "Default")
      (node (ref "IC2") (pin "8") (pinfunction "OUT_8") (pintype "output"))
      (node (ref "R14") (pin "2") (pinfunction "2_2") (pintype "passive"))
    )
    (net (code "28") (name "Net-(IC2D--IN)") (class "Default")
      (node (ref "IC2") (pin "13") (pinfunction "-IN_13") (pintype "input"))
      (node (ref "R1") (pin "1") (pinfunction "1_1") (pintype "passive"))
      (node (ref "R10") (pin "2") (pinfunction "2_2") (pintype "passive"))
      (node (ref "R11") (pin "1") (pinfunction "1_1") (pintype "passive"))
    )
    (net (code "29") (name "Net-(IC2D-OUT)") (class "Default")
      (node (ref "IC2") (pin "14") (pinfunction "OUT_14") (pintype "output"))
      (node (ref "R10") (pin "1") (pinfunction "1_1") (pintype "passive"))
      (node (ref "R29") (pin "2") (pinfunction "2_2") (pintype "passive"))
    )
    (net (code "30") (name "Net-(Q1A-E)") (class "Default")
      (node (ref "Q1") (pin "4") (pinfunction "E_4") (pintype "passive"))
      (node (ref "Q1") (pin "5") (pinfunction "E_5") (pintype "passive"))
      (node (ref "Q3") (pin "4") (pinfunction "E_4") (pintype "passive"))
      (node (ref "Q3") (pin "5") (pinfunction "E_5") (pintype "passive"))
      (node (ref "R14") (pin "1") (pinfunction "1_1") (pintype "passive"))
    )
    (net (code "31") (name "Net-(Q2A-B)") (class "Default")
      (node (ref "Q2") (pin "1") (pinfunction "B_1") (pintype "passive"))
      (node (ref "R38") (pin "1") (pinfunction "1_1") (pintype "passive"))
    )
    (net (code "32") (name "Net-(Q2A-E)") (class "Default")
      (node (ref "Q2") (pin "4") (pinfunction "E_4") (pintype "passive"))
      (node (ref "Q2") (pin "5") (pinfunction "E_5") (pintype "passive"))
      (node (ref "R29") (pin "1") (pinfunction "1_1") (pintype "passive"))
    )
    (net (code "33") (name "Net-(Q2B-B)") (class "Default")
      (node (ref "Q2") (pin "2") (pinfunction "B_2") (pintype "passive"))
      (node (ref "R37") (pin "1") (pinfunction "1_1") (pintype "passive"))
      (node (ref "R4") (pin "1") (pinfunction "1_1") (pintype "passive"))
    )
    (net (code "34") (name "Net-(Q4A-B)") (class "Default")
      (node (ref "Q4") (pin "1") (pinfunction "B_1") (pintype "passive"))
      (node (ref "R20") (pin "2") (pinfunction "2_2") (pintype "passive"))
      (node (ref "R32") (pin "1") (pinfunction "1_1") (pintype "passive"))
    )
    (net (code "35") (name "Net-(Q4A-E)") (class "Default")
      (node (ref "Q4") (pin "4") (pinfunction "E_4") (pintype "passive"))
      (node (ref "Q4") (pin "5") (pinfunction "E_5") (pintype "passive"))
      (node (ref "R15") (pin "1") (pinfunction "1_1") (pintype "passive"))
    )
    (net (code "36") (name "Net-(Q4B-B)") (class "Default")
      (node (ref "Q4") (pin "2") (pinfunction "B_2") (pintype "passive"))
      (node (ref "R19") (pin "1") (pinfunction "1_1") (pintype "passive"))
      (node (ref "R31") (pin "1") (pinfunction "1_1") (pintype "passive"))
    )
    (net (code "37") (name "Net-(Q5A-B)") (class "Default")
      (node (ref "Q5") (pin "1") (pinfunction "B_1") (pintype "passive"))
      (node (ref "R24") (pin "2") (pinfunction "2_2") (pintype "passive"))
      (node (ref "R34") (pin "1") (pinfunction "1_1") (pintype "passive"))
    )
    (net (code "38") (name "Net-(Q5A-E)") (class "Default")
      (node (ref "Q5") (pin "4") (pinfunction "E_4") (pintype "passive"))
      (node (ref "Q5") (pin "5") (pinfunction "E_5") (pintype "passive"))
      (node (ref "R16") (pin "1") (pinfunction "1_1") (pintype "passive"))
    )
    (net (code "39") (name "Net-(Q5B-B)") (class "Default")
      (node (ref "Q5") (pin "2") (pinfunction "B_2") (pintype "passive"))
      (node (ref "R22") (pin "1") (pinfunction "1_1") (pintype "passive"))
      (node (ref "R33") (pin "1") (pinfunction "1_1") (pintype "passive"))
    )
    (net (code "40") (name "Net-(Q6A-B)") (class "Default")
      (node (ref "Q6") (pin "1") (pinfunction "B_1") (pintype "passive"))
      (node (ref "R25") (pin "1") (pinfunction "1_1") (pintype "passive"))
      (node (ref "R27") (pin "2") (pinfunction "2_2") (pintype "passive"))
      (node (ref "R36") (pin "1") (pinfunction "1_1") (pintype "passive"))
    )
    (net (code "41") (name "Net-(Q6A-E)") (class "Default")
      (node (ref "Q6") (pin "4") (pinfunction "E_4") (pintype "passive"))
      (node (ref "Q6") (pin "5") (pinfunction "E_5") (pintype "passive"))
      (node (ref "R17") (pin "1") (pinfunction "1_1") (pintype "passive"))
    )
    (net (code "42") (name "Net-(Q6B-B)") (class "Default")
      (node (ref "Q6") (pin "2") (pinfunction "B_2") (pintype "passive"))
      (node (ref "R35") (pin "1") (pinfunction "1_1") (pintype "passive"))
    )
    (net (code "43") (name "Net-(Q10A-B)") (class "Default")
      (node (ref "Q10") (pin "1") (pinfunction "B_1") (pintype "passive"))
      (node (ref "Q10") (pin "2") (pinfunction "B_2") (pintype "passive"))
      (node (ref "Q10") (pin "3") (pinfunction "C_3") (pintype "passive"))
      (node (ref "Q2") (pin "3") (pinfunction "C_3") (pintype "passive"))
    )
    (net (code "44") (name "Net-(Q10A-C)") (class "Default")
      (node (ref "Q10") (pin "6") (pinfunction "C_6") (pintype "passive"))
      (node (ref "Q15") (pin "1") (pinfunction "B_1") (pintype "passive"))
      (node (ref "Q2") (pin "6") (pinfunction "C_6") (pintype "passive"))
      (node (ref "R13") (pin "1") (pinfunction "1_1") (pintype "passive"))
    )
    (net (code "45") (name "Net-(Q11-B)") (class "Default")
      (node (ref "C8") (pin "1") (pinfunction "1_1") (pintype "passive"))
      (node (ref "Q11") (pin "1") (pinfunction "B_1") (pintype "passive"))
      (node (ref "Q21") (pin "3") (pinfunction "C_3") (pintype "passive"))
      (node (ref "Q5") (pin "6") (pinfunction "C_6") (pintype "passive"))
    )
    (net (code "46") (name "Net-(Q11-E)") (class "Default")
      (node (ref "Q11") (pin "2") (pinfunction "E_2") (pintype "passive"))
      (node (ref "Q12") (pin "1") (pinfunction "B_1") (pintype "passive"))
    )
    (net (code "47") (name "Net-(Q13-B)") (class "Default")
      (node (ref "C9") (pin "1") (pinfunction "1_1") (pintype "passive"))
      (node (ref "Q13") (pin "1") (pinfunction "B_1") (pintype "passive"))
      (node (ref "Q19") (pin "3") (pinfunction "C_3") (pintype "passive"))
      (node (ref "Q6") (pin "6") (pinfunction "C_6") (pintype "passive"))
    )
    (net (code "48") (name "Net-(Q13-E)") (class "Default")
      (node (ref "Q13") (pin "2") (pinfunction "E_2") (pintype "passive"))
      (node (ref "Q14") (pin "1") (pinfunction "B_1") (pintype "passive"))
    )
    (net (code "49") (name "Net-(Q15-E)") (class "Default")
      (node (ref "Q15") (pin "2") (pinfunction "E_2") (pintype "passive"))
      (node (ref "Q16") (pin "1") (pinfunction "B_1") (pintype "passive"))
    )
    (net (code "50") (name "Net-(Q16-E)") (class "Default")
      (node (ref "C12") (pin "1") (pinfunction "1_1") (pintype "passive"))
      (node (ref "Q16") (pin "2") (pinfunction "E_2") (pintype "passive"))
      (node (ref "R18") (pin "1") (pinfunction "1_1") (pintype "passive"))
    )
    (net (code "51") (name "Net-(Q17-B)") (class "Default")
      (node (ref "C7") (pin "1") (pinfunction "1_1") (pintype "passive"))
      (node (ref "Q17") (pin "1") (pinfunction "B_1") (pintype "passive"))
      (node (ref "Q20") (pin "3") (pinfunction "C_3") (pintype "passive"))
      (node (ref "Q4") (pin "6") (pinfunction "C_6") (pintype "passive"))
    )
    (net (code "52") (name "Net-(Q17-E)") (class "Default")
      (node (ref "Q17") (pin "2") (pinfunction "E_2") (pintype "passive"))
      (node (ref "Q18") (pin "1") (pinfunction "B_1") (pintype "passive"))
    )
    (net (code "53") (name "Net-(Q19-B)") (class "Default")
      (node (ref "Q19") (pin "1") (pinfunction "B_1") (pintype "passive"))
      (node (ref "Q6") (pin "3") (pinfunction "C_3") (pintype "passive"))
      (node (ref "Q9") (pin "6") (pinfunction "C_6") (pintype "passive"))
    )
    (net (code "54") (name "Net-(Q19-E)") (class "Default")
      (node (ref "Q19") (pin "2") (pinfunction "E_2") (pintype "passive"))
      (node (ref "Q9") (pin "1") (pinfunction "B_1") (pintype "passive"))
      (node (ref "Q9") (pin "2") (pinfunction "B_2") (pintype "passive"))
      (node (ref "Q9") (pin "3") (pinfunction "C_3") (pintype "passive"))
    )
    (net (code "55") (name "Net-(Q20-B)") (class "Default")
      (node (ref "Q20") (pin "1") (pinfunction "B_1") (pintype "passive"))
      (node (ref "Q4") (pin "3") (pinfunction "C_3") (pintype "passive"))
      (node (ref "Q7") (pin "6") (pinfunction "C_6") (pintype "passive"))
    )
    (net (code "56") (name "Net-(Q20-E)") (class "Default")
      (node (ref "Q20") (pin "2") (pinfunction "E_2") (pintype "passive"))
      (node (ref "Q7") (pin "1") (pinfunction "B_1") (pintype "passive"))
      (node (ref "Q7") (pin "2") (pinfunction "B_2") (pintype "passive"))
      (node (ref "Q7") (pin "3") (pinfunction "C_3") (pintype "passive"))
    )
    (net (code "57") (name "Net-(Q21-B)") (class "Default")
      (node (ref "Q21") (pin "1") (pinfunction "B_1") (pintype "passive"))
      (node (ref "Q5") (pin "3") (pinfunction "C_3") (pintype "passive"))
      (node (ref "Q8") (pin "6") (pinfunction "C_6") (pintype "passive"))
    )
    (net (code "58") (name "Net-(Q21-E)") (class "Default")
      (node (ref "Q21") (pin "2") (pinfunction "E_2") (pintype "passive"))
      (node (ref "Q8") (pin "1") (pinfunction "B_1") (pintype "passive"))
      (node (ref "Q8") (pin "2") (pinfunction "B_2") (pintype "passive"))
      (node (ref "Q8") (pin "3") (pinfunction "C_3") (pintype "passive"))
    )
    (net (code "59") (name "Net-(R41-Pad2)") (class "Default")
      (node (ref "R41") (pin "2") (pinfunction "2_2") (pintype "passive"))
      (node (ref "R42") (pin "1") (pinfunction "1_1") (pintype "passive"))
    )
    (net (code "60") (name "Net-(RV1-A)") (class "Default")
      (node (ref "R43") (pin "1") (pinfunction "1_1") (pintype "passive"))
      (node (ref "RV1") (pin "1") (pinfunction "A_1") (pintype "passive"))
    )
    (net (code "61") (name "Net-(RV1-S)") (class "Default")
      (node (ref "R9") (pin "2") (pinfunction "2_2") (pintype "passive"))
      (node (ref "RV1") (pin "2") (pinfunction "S_2") (pintype "passive"))
    )
    (net (code "62") (name "Net-(RV2-S)") (class "Default")
      (node (ref "R8") (pin "2") (pinfunction "2_2") (pintype "passive"))
      (node (ref "RV2") (pin "2") (pinfunction "S_2") (pintype "passive"))
    )
    (net (code "63") (name "Net-(RV3-S)") (class "Default")
      (node (ref "R11") (pin "2") (pinfunction "2_2") (pintype "passive"))
      (node (ref "RV3") (pin "2") (pinfunction "S_2") (pintype "passive"))
    )
    (net (code "64") (name "Net-(RV4-S)") (class "Default")
      (node (ref "R1") (pin "2") (pinfunction "2_2") (pintype "passive"))
      (node (ref "RV4") (pin "2") (pinfunction "S_2") (pintype "passive"))
    )
    (net (code "65") (name "Net-(RV5-S)") (class "Default")
      (node (ref "R3") (pin "2") (pinfunction "2_2") (pintype "passive"))
      (node (ref "RV5") (pin "2") (pinfunction "S_2") (pintype "passive"))
    )
    (net (code "66") (name "Net-(RV6-A)") (class "Default")
      (node (ref "R6") (pin "1") (pinfunction "1_1") (pintype "passive"))
      (node (ref "RV6") (pin "1") (pinfunction "A_1") (pintype "passive"))
    )
    (net (code "67") (name "OUT_1") (class "Default")
      (node (ref "Q18") (pin "2") (pinfunction "E_2") (pintype "passive"))
      (node (ref "R20") (pin "1") (pinfunction "1_1") (pintype "passive"))
      (node (ref "R21") (pin "1") (pinfunction "1_1") (pintype "passive"))
      (node (ref "R22") (pin "2") (pinfunction "2_2") (pintype "passive"))
    )
    (net (code "68") (name "OUT_2") (class "Default")
      (node (ref "Q12") (pin "2") (pinfunction "E_2") (pintype "passive"))
      (node (ref "R23") (pin "1") (pinfunction "1_1") (pintype "passive"))
      (node (ref "R24") (pin "1") (pinfunction "1_1") (pintype "passive"))
      (node (ref "R25") (pin "2") (pinfunction "2_2") (pintype "passive"))
      (node (ref "X1") (pin "9") (pinfunction "1_9") (pintype "passive"))
    )
    (net (code "69") (name "OUT_TO_FB") (class "Default")
      (node (ref "IC1") (pin "8") (pinfunction "OUT_8") (pintype "output"))
      (node (ref "R4") (pin "2") (pinfunction "2_2") (pintype "passive"))
      (node (ref "R5") (pin "1") (pinfunction "1_1") (pintype "passive"))
      (node (ref "X1") (pin "12") (pinfunction "1_12") (pintype "passive"))
    )
    (net (code "70") (name "Q_IN") (class "Default")
      (node (ref "RV4") (pin "3") (pinfunction "E_3") (pintype "passive"))
      (node (ref "X1") (pin "3") (pinfunction "1_3") (pintype "passive"))
    )
    (net (code "71") (name "unconnected-(IC3-REF-Pad1)") (class "Default")
      (node (ref "IC3") (pin "1") (pinfunction "REF_1") (pintype "no_connect"))
    )
    (net (code "72") (name "unconnected-(RV6-E-Pad3)") (class "Default")
      (node (ref "RV6") (pin "3") (pinfunction "E_3") (pintype "passive"))
    )
    (net (code "73") (name "unconnected-(SV1-Pad11)") (class "Default")
      (node (ref "SV1") (pin "11") (pinfunction "11_11") (pintype "passive"))
    )
    (net (code "74") (name "unconnected-(SV1-Pad12)") (class "Default")
      (node (ref "SV1") (pin "12") (pinfunction "12_12") (pintype "passive"))
    )
    (net (code "75") (name "unconnected-(SV1-Pad13)") (class "Default")
      (node (ref "SV1") (pin "13") (pinfunction "13_13") (pintype "passive"))
    )
    (net (code "76") (name "unconnected-(SV1-Pad14)") (class "Default")
      (node (ref "SV1") (pin "14") (pinfunction "14_14") (pintype "passive"))
    )
    (net (code "77") (name "unconnected-(SV1-Pad15)") (class "Default")
      (node (ref "SV1") (pin "15") (pinfunction "15_15") (pintype "passive"))
    )
    (net (code "78") (name "unconnected-(SV1-Pad16)") (class "Default")
      (node (ref "SV1") (pin "16") (pinfunction "16_16") (pintype "passive"))
    )
  )
)
